# WUST_DEMO.net
KiCad netlist of a schematic drawn in Altium Designer
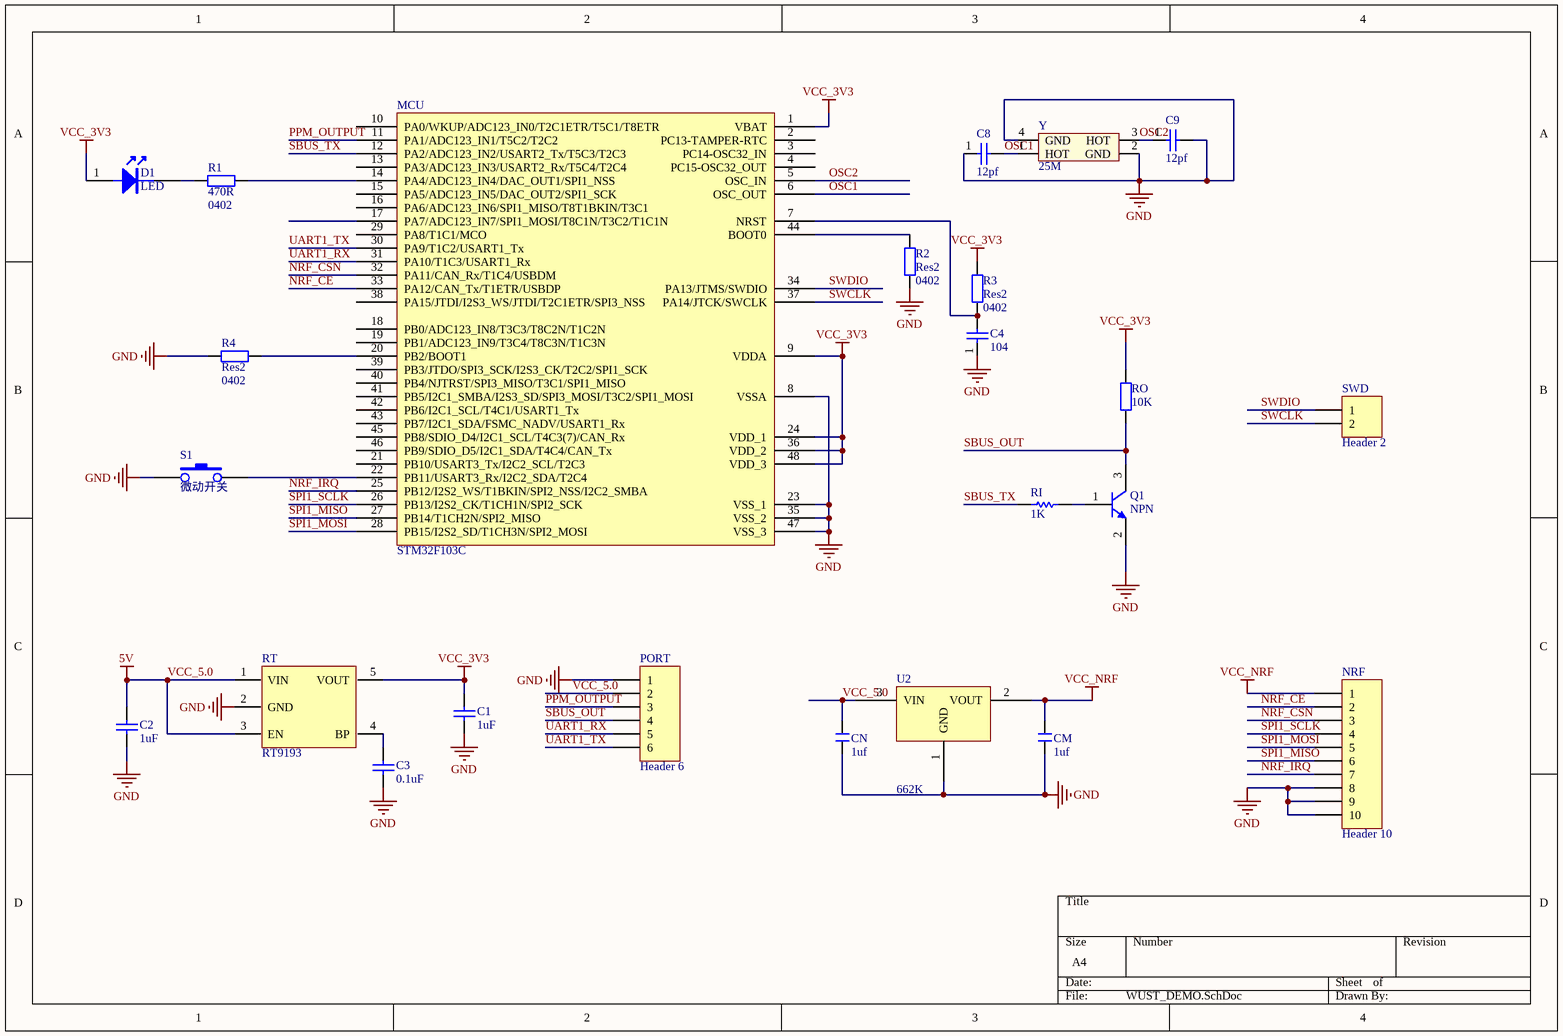
[diagram p0: WUST_DEMO.SchDoc]

(export (version "E")
  (design (tool "Eeschema 10.0.6"))
  (components
    (comp (ref "C1")
      (value "1uF")
      (footprint "0603C")
      (description "无极性电容")
      (fields (field (name "Comment") "Cap") (field (name "PUBLISHER") "Altium Limited"))
      (libsource (lib "fszhang") (part "Cap"))
    )
    (comp (ref "C2")
      (value "1uF")
      (footprint "0603C")
      (description "无极性电容")
      (fields (field (name "Comment") "Cap") (field (name "PUBLISHER") "Altium Limited"))
      (libsource (lib "fszhang") (part "Cap"))
    )
    (comp (ref "C3")
      (value "0.1uF")
      (footprint "0402C")
      (description "无极性电容")
      (fields (field (name "Comment") "Cap") (field (name "PUBLISHER") "Altium Limited"))
      (libsource (lib "fszhang") (part "Cap"))
    )
    (comp (ref "C4")
      (value "104")
      (footprint "0402C")
      (fields (field (name "Comment") "Cap"))
      (libsource (lib "Smartcar") (part "Cap-0.1Uf"))
    )
    (comp (ref "C8")
      (value "12pf")
      (footprint "0402C")
      (fields (field (name "Comment") "Cap"))
      (libsource (lib "Smartcar") (part "Cap-0.1Uf"))
    )
    (comp (ref "C9")
      (value "12pf")
      (footprint "0402C")
      (fields (field (name "Comment") "Cap"))
      (libsource (lib "Smartcar") (part "Cap-0.1Uf"))
    )
    (comp (ref "CM")
      (value "1uf")
      (footprint "0603C")
      (description "无极性贴片电容")
      (fields (field (name "版权归属") "源创客"))
      (libsource (lib "NCQ_MSP432") (part "C"))
    )
    (comp (ref "CN")
      (value "1uf")
      (footprint "0603C")
      (description "无极性贴片电容")
      (fields (field (name "版权归属") "源创客"))
      (libsource (lib "NCQ_MSP432") (part "C"))
    )
    (comp (ref "D1") (value "LED") (footprint "0603_LED") (libsource (lib "Smartcar") (part "Led0")))
    (comp (ref "MCU")
      (value "STM32F103C")
      (footprint "LQFP-48_7x7x05P")
      (description "STM32单片机48引脚")
      (libsource (lib "Fszhang") (part "STM32F103C"))
    )
    (comp (ref "NRF")
      (value "Header 10")
      (footprint "PE01-ML01SP4")
      (description "Header, 10-Pin")
      (fields (field (name "PUBLISHER") "Altium Limited"))
      (libsource (lib "Miscellaneous Connectors") (part "Header 10"))
    )
    (comp (ref "PORT")
      (value "Header 6")
      (footprint "1.25_6P")
      (description "Header, 6-Pin")
      (fields (field (name "PUBLISHER") "Altium Limited"))
      (libsource (lib "Miscellaneous Connectors") (part "Header 6"))
    )
    (comp (ref "Q1") (value "NPN") (footprint "SOT23_N") (libsource (lib "Smartcar") (part "NPN")))
    (comp (ref "R1")
      (value "470R")
      (footprint "0402R")
      (description "Resistor")
      (fields (field (name "ALTIUM_VALUE") "0402") (field (name "PUBLISHER") "Altium Limited"))
      (libsource (lib "") (part "Res2_3"))
    )
    (comp (ref "R2")
      (value "Res2")
      (footprint "0402R")
      (description "Resistor")
      (fields (field (name "ALTIUM_VALUE") "0402") (field (name "PUBLISHER") "Altium Limited"))
      (libsource (lib "") (part "Res2_2"))
    )
    (comp (ref "R3")
      (value "Res2")
      (footprint "0402R")
      (description "Resistor")
      (fields (field (name "ALTIUM_VALUE") "0402") (field (name "PUBLISHER") "Altium Limited"))
      (libsource (lib "Miscellaneous Devices") (part "Res2"))
    )
    (comp (ref "R4")
      (value "Res2")
      (footprint "0402R")
      (description "Resistor")
      (fields (field (name "ALTIUM_VALUE") "0402") (field (name "PUBLISHER") "Altium Limited"))
      (libsource (lib "") (part "Res2_1"))
    )
    (comp (ref "RI")
      (value "1K")
      (footprint "0402R")
      (fields (field (name "Comment") "res1"))
      (libsource (lib "Smartcar") (part "res1"))
    )
    (comp (ref "RO")
      (value "10K")
      (footprint "0402R")
      (description "贴片电阻")
      (fields (field (name "Comment") "Res1") (field (name "PUBLISHER") "Altium Limited"))
      (libsource (lib "fszhang") (part "Res1"))
    )
    (comp (ref "RT") (value "RT9193") (footprint "SOT23_5") (libsource (lib "飞控板") (part "RT9193")))
    (comp (ref "S1") (value "微动开关") (footprint "KEY3420P") (libsource (lib "开关") (part "微动开关")))
    (comp (ref "SWD")
      (value "Header 2")
      (footprint "pad")
      (description "Header, 2-Pin")
      (fields (field (name "PUBLISHER") "Altium Limited"))
      (libsource (lib "Miscellaneous Connectors") (part "Header 2"))
    )
    (comp (ref "U2") (value "662K") (footprint "SOT23-3N") (libsource (lib "self-used") (part "662K")))
    (comp (ref "Y")
      (value "25M")
      (footprint "SMD-3225_4P")
      (description "3225贴片无源晶振")
      (libsource (lib "OpenMVX") (part "XTAL_3225"))
    )
  )
  (nets
    (net (code "1") (name "/NRF_CE") (class "Default")
      (node (ref "MCU") (pin "33") (pinfunction "PA12/CAN_Tx/T1ETR/USBDP_33") (pintype "passive"))
      (node (ref "NRF") (pin "2") (pinfunction "2_2") (pintype "passive"))
    )
    (net (code "2") (name "/NRF_CSN") (class "Default")
      (node (ref "MCU") (pin "32") (pinfunction "PA11/CAN_Rx/T1C4/USBDM_32") (pintype "passive"))
      (node (ref "NRF") (pin "3") (pinfunction "3_3") (pintype "passive"))
    )
    (net (code "3") (name "/NRF_IRQ") (class "Default")
      (node (ref "MCU") (pin "25") (pinfunction "PB12/I2S2_WS/T1BKIN/SPI2_NSS/I2C2_SMBA_25") (pintype "passive"))
      (node (ref "NRF") (pin "7") (pinfunction "7_7") (pintype "passive"))
    )
    (net (code "4") (name "/OSC1") (class "Default")
      (node (ref "C8") (pin "2") (pinfunction "2_2") (pintype "passive"))
      (node (ref "MCU") (pin "6") (pinfunction "OSC_OUT_6") (pintype "passive"))
      (node (ref "Y") (pin "1") (pinfunction "HOT_1") (pintype "passive"))
    )
    (net (code "5") (name "/OSC2") (class "Default")
      (node (ref "C9") (pin "1") (pinfunction "1_1") (pintype "passive"))
      (node (ref "MCU") (pin "5") (pinfunction "OSC_IN_5") (pintype "passive"))
      (node (ref "Y") (pin "3") (pinfunction "HOT_3") (pintype "passive"))
    )
    (net (code "6") (name "/PPM_OUTPUT") (class "Default")
      (node (ref "MCU") (pin "11") (pinfunction "PA1/ADC123_IN1/T5C2/T2C2_11") (pintype "passive"))
      (node (ref "PORT") (pin "3") (pinfunction "3_3") (pintype "passive"))
    )
    (net (code "7") (name "/SBUS_OUT") (class "Default")
      (node (ref "PORT") (pin "4") (pinfunction "4_4") (pintype "passive"))
      (node (ref "Q1") (pin "3") (pinfunction "C_3") (pintype "passive"))
      (node (ref "RO") (pin "1") (pinfunction "1_1") (pintype "passive"))
    )
    (net (code "8") (name "/SBUS_TX") (class "Default")
      (node (ref "MCU") (pin "12") (pinfunction "PA2/ADC123_IN2/USART2_Tx/T5C3/T2C3_12") (pintype "passive"))
      (node (ref "RI") (pin "1") (pinfunction "1_1") (pintype "passive"))
    )
    (net (code "9") (name "/SPI1_MISO") (class "Default")
      (node (ref "MCU") (pin "27") (pinfunction "PB14/T1CH2N/SPI2_MISO_27") (pintype "passive"))
      (node (ref "NRF") (pin "6") (pinfunction "6_6") (pintype "passive"))
    )
    (net (code "10") (name "/SPI1_MOSI") (class "Default")
      (node (ref "MCU") (pin "28") (pinfunction "PB15/I2S2_SD/T1CH3N/SPI2_MOSI_28") (pintype "passive"))
      (node (ref "NRF") (pin "5") (pinfunction "5_5") (pintype "passive"))
    )
    (net (code "11") (name "/SPI1_SCLK") (class "Default")
      (node (ref "MCU") (pin "26") (pinfunction "PB13/I2S2_CK/T1CH1N/SPI2_SCK_26") (pintype "passive"))
      (node (ref "NRF") (pin "4") (pinfunction "4_4") (pintype "passive"))
    )
    (net (code "12") (name "/SWCLK") (class "Default")
      (node (ref "MCU") (pin "37") (pinfunction "PA14/JTCK/SWCLK_37") (pintype "passive"))
      (node (ref "SWD") (pin "2") (pinfunction "2_2") (pintype "passive"))
    )
    (net (code "13") (name "/SWDIO") (class "Default")
      (node (ref "MCU") (pin "34") (pinfunction "PA13/JTMS/SWDIO_34") (pintype "passive"))
      (node (ref "SWD") (pin "1") (pinfunction "1_1") (pintype "passive"))
    )
    (net (code "14") (name "/UART1_RX") (class "Default")
      (node (ref "MCU") (pin "31") (pinfunction "PA10/T1C3/USART1_Rx_31") (pintype "passive"))
      (node (ref "PORT") (pin "5") (pinfunction "5_5") (pintype "passive"))
    )
    (net (code "15") (name "/UART1_TX") (class "Default")
      (node (ref "MCU") (pin "30") (pinfunction "PA9/T1C2/USART1_Tx_30") (pintype "passive"))
      (node (ref "PORT") (pin "6") (pinfunction "6_6") (pintype "passive"))
    )
    (net (code "16") (name "5V") (class "Default")
      (node (ref "C2") (pin "2") (pinfunction "2_2") (pintype "passive"))
      (node (ref "CN") (pin "2") (pinfunction "2_2") (pintype "passive"))
      (node (ref "PORT") (pin "2") (pinfunction "2_2") (pintype "passive"))
      (node (ref "RT") (pin "1") (pinfunction "VIN_1") (pintype "passive"))
      (node (ref "RT") (pin "3") (pinfunction "EN_3") (pintype "passive"))
      (node (ref "U2") (pin "3") (pinfunction "VIN_3") (pintype "passive"))
    )
    (net (code "17") (name "GND") (class "Default")
      (node (ref "C1") (pin "1") (pinfunction "1_1") (pintype "passive"))
      (node (ref "C2") (pin "1") (pinfunction "1_1") (pintype "passive"))
      (node (ref "C3") (pin "1") (pinfunction "1_1") (pintype "passive"))
      (node (ref "C4") (pin "1") (pinfunction "1_1") (pintype "passive"))
      (node (ref "C8") (pin "1") (pinfunction "1_1") (pintype "passive"))
      (node (ref "C9") (pin "2") (pinfunction "2_2") (pintype "passive"))
      (node (ref "CM") (pin "1") (pinfunction "1_1") (pintype "passive"))
      (node (ref "CN") (pin "1") (pinfunction "1_1") (pintype "passive"))
      (node (ref "MCU") (pin "23") (pinfunction "VSS_1_23") (pintype "passive"))
      (node (ref "MCU") (pin "35") (pinfunction "VSS_2_35") (pintype "passive"))
      (node (ref "MCU") (pin "47") (pinfunction "VSS_3_47") (pintype "passive"))
      (node (ref "MCU") (pin "8") (pinfunction "VSSA_8") (pintype "passive"))
      (node (ref "NRF") (pin "10") (pinfunction "10_10") (pintype "passive"))
      (node (ref "NRF") (pin "8") (pinfunction "8_8") (pintype "passive"))
      (node (ref "NRF") (pin "9") (pinfunction "9_9") (pintype "passive"))
      (node (ref "PORT") (pin "1") (pinfunction "1_1") (pintype "passive"))
      (node (ref "Q1") (pin "2") (pinfunction "E_2") (pintype "passive"))
      (node (ref "R2") (pin "1") (pinfunction "1_1") (pintype "passive"))
      (node (ref "R4") (pin "2") (pinfunction "2_2") (pintype "passive"))
      (node (ref "RT") (pin "2") (pinfunction "GND_2") (pintype "passive"))
      (node (ref "S1") (pin "1") (pinfunction "1_1") (pintype "passive"))
      (node (ref "U2") (pin "1") (pinfunction "GND_1") (pintype "passive"))
      (node (ref "Y") (pin "2") (pinfunction "GND_2") (pintype "passive"))
      (node (ref "Y") (pin "4") (pinfunction "GND_4") (pintype "passive"))
    )
    (net (code "18") (name "Net-(D1-Pad2)") (class "Default")
      (node (ref "D1") (pin "2") (pinfunction "2_2") (pintype "passive"))
      (node (ref "R1") (pin "2") (pinfunction "2_2") (pintype "passive"))
    )
    (net (code "19") (name "Net-(MCU-BOOT0)") (class "Default")
      (node (ref "MCU") (pin "44") (pinfunction "BOOT0_44") (pintype "passive"))
      (node (ref "R2") (pin "2") (pinfunction "2_2") (pintype "passive"))
    )
    (net (code "20") (name "Net-(MCU-NRST)") (class "Default")
      (node (ref "C4") (pin "2") (pinfunction "2_2") (pintype "passive"))
      (node (ref "MCU") (pin "7") (pinfunction "NRST_7") (pintype "passive"))
      (node (ref "R3") (pin "1") (pinfunction "1_1") (pintype "passive"))
    )
    (net (code "21") (name "Net-(MCU-PA4{slash}ADC123_IN4{slash}DAC_OUT1{slash}SPI1_NSS)") (class "Default")
      (node (ref "MCU") (pin "14") (pinfunction "PA4/ADC123_IN4/DAC_OUT1/SPI1_NSS_14") (pintype "passive"))
      (node (ref "R1") (pin "1") (pinfunction "1_1") (pintype "passive"))
    )
    (net (code "22") (name "Net-(MCU-PB2{slash}BOOT1)") (class "Default")
      (node (ref "MCU") (pin "20") (pinfunction "PB2/BOOT1_20") (pintype "passive"))
      (node (ref "R4") (pin "1") (pinfunction "1_1") (pintype "passive"))
    )
    (net (code "23") (name "Net-(MCU-PB11{slash}USART3_Rx{slash}I2C2_SDA{slash}T2C4)") (class "Default")
      (node (ref "MCU") (pin "22") (pinfunction "PB11/USART3_Rx/I2C2_SDA/T2C4_22") (pintype "passive"))
      (node (ref "S1") (pin "2") (pinfunction "2_2") (pintype "passive"))
    )
    (net (code "24") (name "Net-(Q1-B)") (class "Default")
      (node (ref "Q1") (pin "1") (pinfunction "B_1") (pintype "passive"))
      (node (ref "RI") (pin "2") (pinfunction "2_2") (pintype "passive"))
    )
    (net (code "25") (name "Net-(RT-BP)") (class "Default")
      (node (ref "C3") (pin "2") (pinfunction "2_2") (pintype "passive"))
      (node (ref "RT") (pin "4") (pinfunction "BP_4") (pintype "passive"))
    )
    (net (code "26") (name "VCC_3V3") (class "Default")
      (node (ref "C1") (pin "2") (pinfunction "2_2") (pintype "passive"))
      (node (ref "D1") (pin "1") (pinfunction "1_1") (pintype "passive"))
      (node (ref "MCU") (pin "1") (pinfunction "VBAT_1") (pintype "passive"))
      (node (ref "MCU") (pin "24") (pinfunction "VDD_1_24") (pintype "passive"))
      (node (ref "MCU") (pin "36") (pinfunction "VDD_2_36") (pintype "passive"))
      (node (ref "MCU") (pin "48") (pinfunction "VDD_3_48") (pintype "passive"))
      (node (ref "MCU") (pin "9") (pinfunction "VDDA_9") (pintype "passive"))
      (node (ref "R3") (pin "2") (pinfunction "2_2") (pintype "passive"))
      (node (ref "RO") (pin "2") (pinfunction "2_2") (pintype "passive"))
      (node (ref "RT") (pin "5") (pinfunction "VOUT_5") (pintype "passive"))
    )
    (net (code "27") (name "VCC_NRF") (class "Default")
      (node (ref "CM") (pin "2") (pinfunction "2_2") (pintype "passive"))
      (node (ref "NRF") (pin "1") (pinfunction "1_1") (pintype "passive"))
      (node (ref "U2") (pin "2") (pinfunction "VOUT_2") (pintype "passive"))
    )
    (net (code "28") (name "unconnected-(MCU-PA0{slash}WKUP{slash}ADC123_IN0{slash}T2C1ETR{slash}T5C1{slash}T8ETR-Pad10)") (class "Default")
      (node (ref "MCU") (pin "10") (pinfunction "PA0/WKUP/ADC123_IN0/T2C1ETR/T5C1/T8ETR_10") (pintype "passive"))
    )
    (net (code "29") (name "unconnected-(MCU-PA3{slash}ADC123_IN3{slash}USART2_Rx{slash}T5C4{slash}T2C4-Pad13)") (class "Default")
      (node (ref "MCU") (pin "13") (pinfunction "PA3/ADC123_IN3/USART2_Rx/T5C4/T2C4_13") (pintype "passive"))
    )
    (net (code "30") (name "unconnected-(MCU-PA5{slash}ADC123_IN5{slash}DAC_OUT2{slash}SPI1_SCK-Pad15)") (class "Default")
      (node (ref "MCU") (pin "15") (pinfunction "PA5/ADC123_IN5/DAC_OUT2/SPI1_SCK_15") (pintype "passive"))
    )
    (net (code "31") (name "unconnected-(MCU-PA6{slash}ADC123_IN6{slash}SPI1_MISO{slash}T8T1BKIN{slash}T3C1-Pad16)") (class "Default")
      (node (ref "MCU") (pin "16") (pinfunction "PA6/ADC123_IN6/SPI1_MISO/T8T1BKIN/T3C1_16") (pintype "passive"))
    )
    (net (code "32") (name "unconnected-(MCU-PA7{slash}ADC123_IN7{slash}SPI1_MOSI{slash}T8C1N{slash}T3C2{slash}T1C1N-Pad17)") (class "Default")
      (node (ref "MCU") (pin "17") (pinfunction "PA7/ADC123_IN7/SPI1_MOSI/T8C1N/T3C2/T1C1N_17") (pintype "passive"))
    )
    (net (code "33") (name "unconnected-(MCU-PA8{slash}T1C1{slash}MCO-Pad29)") (class "Default")
      (node (ref "MCU") (pin "29") (pinfunction "PA8/T1C1/MCO_29") (pintype "passive"))
    )
    (net (code "34") (name "unconnected-(MCU-PA15{slash}JTDI{slash}I2S3_WS{slash}JTDI{slash}T2C1ETR{slash}SPI3_NSS-Pad38)") (class "Default")
      (node (ref "MCU") (pin "38") (pinfunction "PA15/JTDI/I2S3_WS/JTDI/T2C1ETR/SPI3_NSS_38") (pintype "passive"))
    )
    (net (code "35") (name "unconnected-(MCU-PB0{slash}ADC123_IN8{slash}T3C3{slash}T8C2N{slash}T1C2N-Pad18)") (class "Default")
      (node (ref "MCU") (pin "18") (pinfunction "PB0/ADC123_IN8/T3C3/T8C2N/T1C2N_18") (pintype "passive"))
    )
    (net (code "36") (name "unconnected-(MCU-PB1{slash}ADC123_IN9{slash}T3C4{slash}T8C3N{slash}T1C3N-Pad19)") (class "Default")
      (node (ref "MCU") (pin "19") (pinfunction "PB1/ADC123_IN9/T3C4/T8C3N/T1C3N_19") (pintype "passive"))
    )
    (net (code "37") (name "unconnected-(MCU-PB3{slash}JTDO{slash}SPI3_SCK{slash}I2S3_CK{slash}T2C2{slash}SPI1_SCK-Pad39)") (class "Default")
      (node (ref "MCU") (pin "39") (pinfunction "PB3/JTDO/SPI3_SCK/I2S3_CK/T2C2/SPI1_SCK_39") (pintype "passive"))
    )
    (net (code "38") (name "unconnected-(MCU-PB4{slash}NJTRST{slash}SPI3_MISO{slash}T3C1{slash}SPI1_MISO-Pad40)") (class "Default")
      (node (ref "MCU") (pin "40") (pinfunction "PB4/NJTRST/SPI3_MISO/T3C1/SPI1_MISO_40") (pintype "passive"))
    )
    (net (code "39") (name "unconnected-(MCU-PB5{slash}I2C1_SMBA{slash}I2S3_SD{slash}SPI3_MOSI{slash}T3C2{slash}SPI1_MOSI-Pad41)") (class "Default")
      (node (ref "MCU") (pin "41") (pinfunction "PB5/I2C1_SMBA/I2S3_SD/SPI3_MOSI/T3C2/SPI1_MOSI_41") (pintype "passive"))
    )
    (net (code "40") (name "unconnected-(MCU-PB6{slash}I2C1_SCL{slash}T4C1{slash}USART1_Tx-Pad42)") (class "Default")
      (node (ref "MCU") (pin "42") (pinfunction "PB6/I2C1_SCL/T4C1/USART1_Tx_42") (pintype "passive"))
    )
    (net (code "41") (name "unconnected-(MCU-PB7{slash}I2C1_SDA{slash}FSMC_NADV{slash}USART1_Rx-Pad43)") (class "Default")
      (node (ref "MCU") (pin "43") (pinfunction "PB7/I2C1_SDA/FSMC_NADV/USART1_Rx_43") (pintype "passive"))
    )
    (net (code "42") (name "unconnected-(MCU-PB8{slash}SDIO_D4{slash}I2C1_SCL{slash}T4C3(7){slash}CAN_Rx-Pad45)") (class "Default")
      (node (ref "MCU") (pin "45") (pinfunction "PB8/SDIO_D4/I2C1_SCL/T4C3(7)/CAN_Rx_45") (pintype "passive"))
    )
    (net (code "43") (name "unconnected-(MCU-PB9{slash}SDIO_D5{slash}I2C1_SDA{slash}T4C4{slash}CAN_Tx-Pad46)") (class "Default")
      (node (ref "MCU") (pin "46") (pinfunction "PB9/SDIO_D5/I2C1_SDA/T4C4/CAN_Tx_46") (pintype "passive"))
    )
    (net (code "44") (name "unconnected-(MCU-PB10{slash}USART3_Tx{slash}I2C2_SCL{slash}T2C3-Pad21)") (class "Default")
      (node (ref "MCU") (pin "21") (pinfunction "PB10/USART3_Tx/I2C2_SCL/T2C3_21") (pintype "passive"))
    )
    (net (code "45") (name "unconnected-(MCU-PC13-TAMPER-RTC-Pad2)") (class "Default")
      (node (ref "MCU") (pin "2") (pinfunction "PC13-TAMPER-RTC_2") (pintype "passive"))
    )
    (net (code "46") (name "unconnected-(MCU-PC14-OSC32_IN-Pad3)") (class "Default")
      (node (ref "MCU") (pin "3") (pinfunction "PC14-OSC32_IN_3") (pintype "passive"))
    )
    (net (code "47") (name "unconnected-(MCU-PC15-OSC32_OUT-Pad4)") (class "Default")
      (node (ref "MCU") (pin "4") (pinfunction "PC15-OSC32_OUT_4") (pintype "passive"))
    )
  )
)
